# rfidbadge.net
KiCad netlist of a schematic drawn in EAGLE
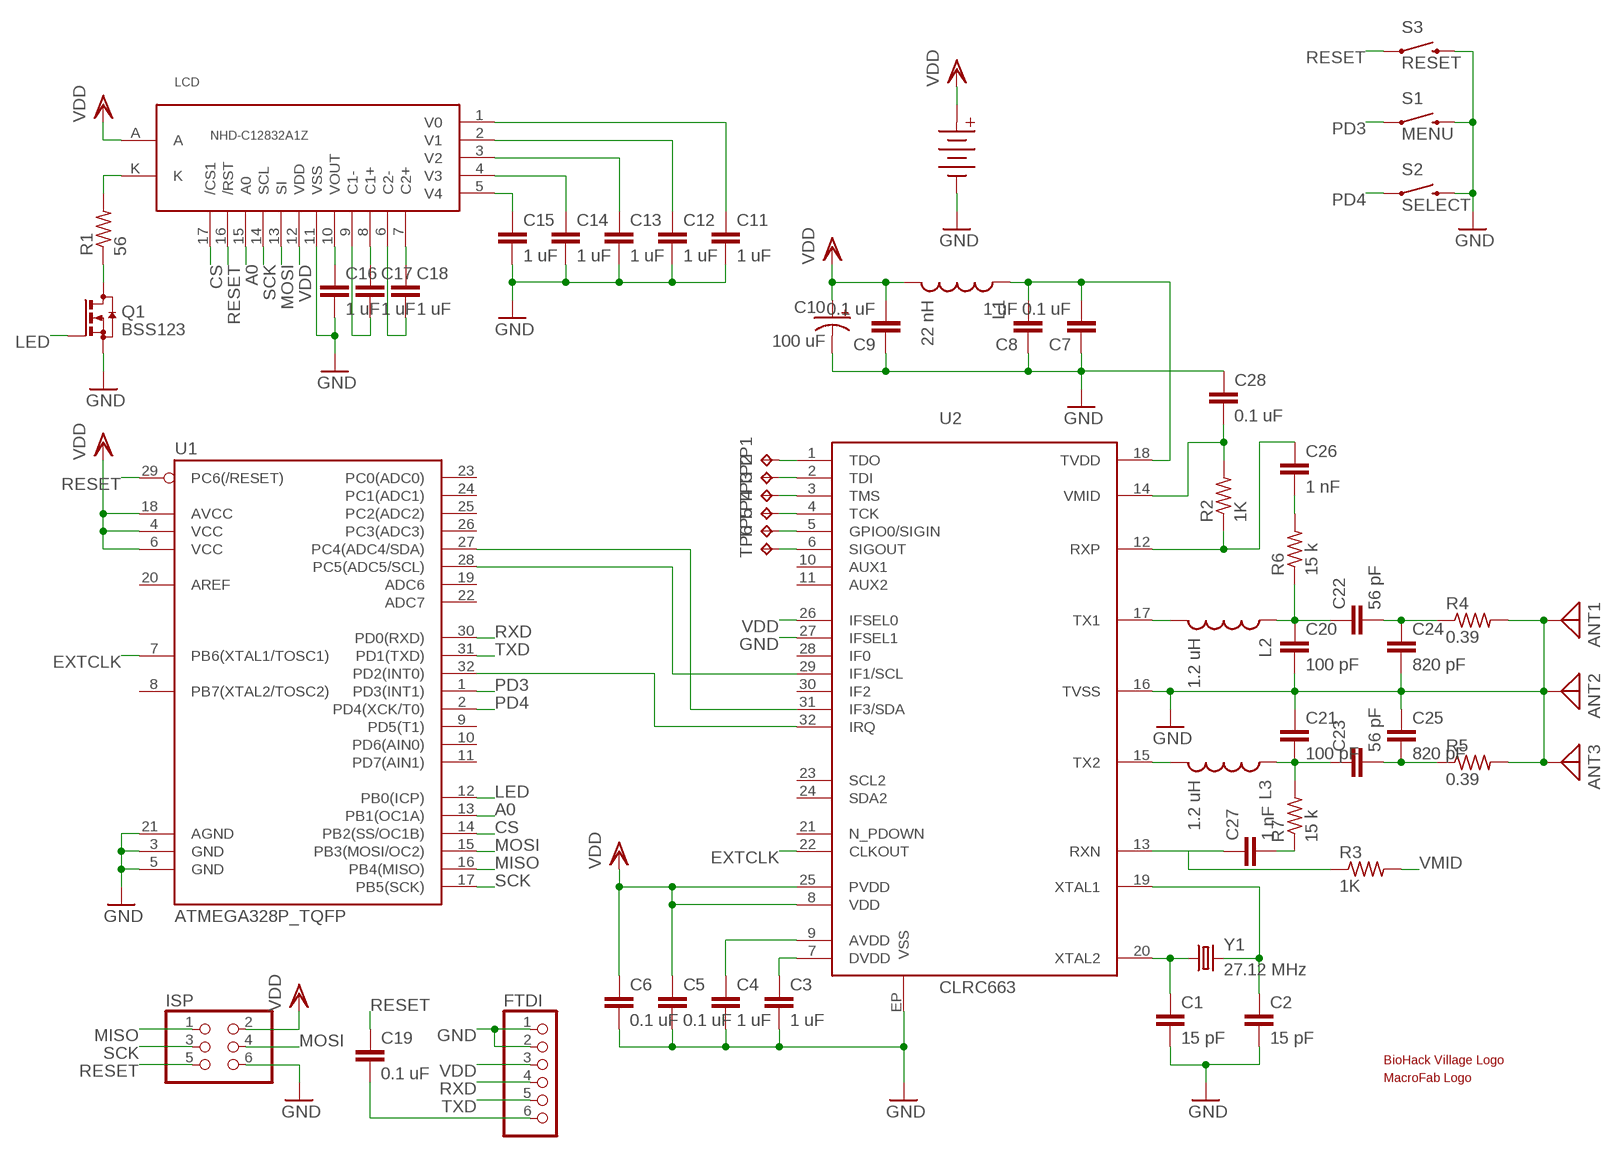
[diagram p0: schematic, sheet 1]

(export (version "E")
  (design (tool "Eeschema 10.0.6"))
  (components
    (comp (ref "ANT1")
      (value "ANTENNA")
      (footprint "eagle-import:PAD-01")
      (libsource (lib "eagle-import") (part "ANTENNA"))
    )
    (comp (ref "ANT2")
      (value "ANTENNA")
      (footprint "eagle-import:PAD-01")
      (libsource (lib "eagle-import") (part "ANTENNA"))
    )
    (comp (ref "ANT3")
      (value "ANTENNA")
      (footprint "eagle-import:PAD-01")
      (libsource (lib "eagle-import") (part "ANTENNA"))
    )
    (comp (ref "BAT")
      (value "AAA_X3")
      (footprint "eagle-import:AAA_X3")
      (libsource (lib "eagle-import") (part "AAA_X3"))
    )
    (comp (ref "C1")
      (value "15 pF")
      (footprint "eagle-import:C0603K")
      (libsource (lib "eagle-import") (part "C-EUC0603K"))
    )
    (comp (ref "C2")
      (value "15 pF")
      (footprint "eagle-import:C0603K")
      (libsource (lib "eagle-import") (part "C-EUC0603K"))
    )
    (comp (ref "C3")
      (value "1 uF")
      (footprint "eagle-import:C0603K")
      (libsource (lib "eagle-import") (part "C-EUC0603K"))
    )
    (comp (ref "C4")
      (value "1 uF")
      (footprint "eagle-import:C0603K")
      (libsource (lib "eagle-import") (part "C-EUC0603K"))
    )
    (comp (ref "C5")
      (value "0.1 uF")
      (footprint "eagle-import:C0603K")
      (libsource (lib "eagle-import") (part "C-EUC0603K"))
    )
    (comp (ref "C6")
      (value "0.1 uF")
      (footprint "eagle-import:C0603K")
      (libsource (lib "eagle-import") (part "C-EUC0603K"))
    )
    (comp (ref "C7")
      (value "0.1 uF")
      (footprint "eagle-import:C0603K")
      (libsource (lib "eagle-import") (part "C-EUC0603K"))
    )
    (comp (ref "C8")
      (value "1 uF")
      (footprint "eagle-import:C0603K")
      (libsource (lib "eagle-import") (part "C-EUC0603K"))
    )
    (comp (ref "C9")
      (value "0.1 uF")
      (footprint "eagle-import:C0603K")
      (libsource (lib "eagle-import") (part "C-EUC0603K"))
    )
    (comp (ref "C10")
      (value "100 uF")
      (footprint "eagle-import:EIA7343")
      (libsource (lib "eagle-import") (part "CAP_POL7343"))
    )
    (comp (ref "C11")
      (value "1 uF")
      (footprint "eagle-import:C0603K")
      (libsource (lib "eagle-import") (part "C-EUC0603K"))
    )
    (comp (ref "C12")
      (value "1 uF")
      (footprint "eagle-import:C0603K")
      (libsource (lib "eagle-import") (part "C-EUC0603K"))
    )
    (comp (ref "C13")
      (value "1 uF")
      (footprint "eagle-import:C0603K")
      (libsource (lib "eagle-import") (part "C-EUC0603K"))
    )
    (comp (ref "C14")
      (value "1 uF")
      (footprint "eagle-import:C0603K")
      (libsource (lib "eagle-import") (part "C-EUC0603K"))
    )
    (comp (ref "C15")
      (value "1 uF")
      (footprint "eagle-import:C0603K")
      (libsource (lib "eagle-import") (part "C-EUC0603K"))
    )
    (comp (ref "C16")
      (value "1 uF")
      (footprint "eagle-import:C0603K")
      (libsource (lib "eagle-import") (part "C-EUC0603K"))
    )
    (comp (ref "C17")
      (value "1 uF")
      (footprint "eagle-import:C0603K")
      (libsource (lib "eagle-import") (part "C-EUC0603K"))
    )
    (comp (ref "C18")
      (value "1 uF")
      (footprint "eagle-import:C0603K")
      (libsource (lib "eagle-import") (part "C-EUC0603K"))
    )
    (comp (ref "C19")
      (value "0.1 uF")
      (footprint "eagle-import:C0603K")
      (libsource (lib "eagle-import") (part "C-EUC0603K"))
    )
    (comp (ref "C20")
      (value "100 pF")
      (footprint "eagle-import:C0603K")
      (libsource (lib "eagle-import") (part "C-EUC0603K"))
    )
    (comp (ref "C21")
      (value "100 pF")
      (footprint "eagle-import:C0603K")
      (libsource (lib "eagle-import") (part "C-EUC0603K"))
    )
    (comp (ref "C22")
      (value "56 pF")
      (footprint "eagle-import:C0603K")
      (libsource (lib "eagle-import") (part "C-EUC0603K"))
    )
    (comp (ref "C23")
      (value "56 pF")
      (footprint "eagle-import:C0603K")
      (libsource (lib "eagle-import") (part "C-EUC0603K"))
    )
    (comp (ref "C24")
      (value "820 pF")
      (footprint "eagle-import:C0603K")
      (libsource (lib "eagle-import") (part "C-EUC0603K"))
    )
    (comp (ref "C25")
      (value "820 pF")
      (footprint "eagle-import:C0603K")
      (libsource (lib "eagle-import") (part "C-EUC0603K"))
    )
    (comp (ref "C26")
      (value "1 nF")
      (footprint "eagle-import:C0603K")
      (libsource (lib "eagle-import") (part "C-EUC0603K"))
    )
    (comp (ref "C27")
      (value "1 nF")
      (footprint "eagle-import:C0603K")
      (libsource (lib "eagle-import") (part "C-EUC0603K"))
    )
    (comp (ref "C28")
      (value "0.1 uF")
      (footprint "eagle-import:C0603K")
      (libsource (lib "eagle-import") (part "C-EUC0603K"))
    )
    (comp (ref "FTDI")
      (value "PINHD-1X6")
      (footprint "eagle-import:1X06")
      (libsource (lib "eagle-import") (part "PINHD-1X6"))
    )
    (comp (ref "ISP")
      (value "PINHD-2X3")
      (footprint "eagle-import:2X03")
      (libsource (lib "eagle-import") (part "PINHD-2X3"))
    )
    (comp (ref "L1")
      (value "22 nH")
      (footprint "eagle-import:0603")
      (fields (field (name "PROD_ID") "1276-6310-1-ND"))
      (libsource (lib "eagle-import") (part "INDUCTOR30OHM,1.8A"))
    )
    (comp (ref "L2")
      (value "1.2 uH")
      (footprint "eagle-import:0603")
      (fields (field (name "PROD_ID") "535-12527-1-ND"))
      (libsource (lib "eagle-import") (part "INDUCTOR30OHM,1.8A"))
    )
    (comp (ref "L3")
      (value "1.2 uH")
      (footprint "eagle-import:0603")
      (fields (field (name "PROD_ID") "535-12527-1-ND"))
      (libsource (lib "eagle-import") (part "INDUCTOR30OHM,1.8A"))
    )
    (comp (ref "LCD")
      (value "NHD-C12832A1Z")
      (footprint "eagle-import:NHD-C12832A1Z")
      (libsource (lib "eagle-import") (part "NHD-C12832A1Z"))
    )
    (comp (ref "Q1")
      (value "BSS123")
      (footprint "eagle-import:SOT23")
      (libsource (lib "eagle-import") (part "BSS123"))
    )
    (comp (ref "R1")
      (value "56")
      (footprint "eagle-import:R0603")
      (libsource (lib "eagle-import") (part "R-US_R0603"))
    )
    (comp (ref "R2")
      (value "1K")
      (footprint "eagle-import:R0603")
      (libsource (lib "eagle-import") (part "R-US_R0603"))
    )
    (comp (ref "R3")
      (value "1K")
      (footprint "eagle-import:R0603")
      (libsource (lib "eagle-import") (part "R-US_R0603"))
    )
    (comp (ref "R4")
      (value "0.39")
      (footprint "eagle-import:R0603")
      (libsource (lib "eagle-import") (part "R-US_R0603"))
    )
    (comp (ref "R5")
      (value "0.39")
      (footprint "eagle-import:R0603")
      (libsource (lib "eagle-import") (part "R-US_R0603"))
    )
    (comp (ref "R6")
      (value "15 k")
      (footprint "eagle-import:R0603")
      (libsource (lib "eagle-import") (part "R-US_R0603"))
    )
    (comp (ref "R7")
      (value "15 k")
      (footprint "eagle-import:R0603")
      (libsource (lib "eagle-import") (part "R-US_R0603"))
    )
    (comp (ref "S1")
      (value "MENU")
      (footprint "eagle-import:TACTILE_SWITCH_TALL")
      (fields (field (name "PROD_ID") "CKN9112CT-ND"))
      (libsource (lib "eagle-import") (part "SWITCH-MOMENTARY-2SMD-4"))
    )
    (comp (ref "S2")
      (value "SELECT")
      (footprint "eagle-import:TACTILE_SWITCH_TALL")
      (fields (field (name "PROD_ID") "CKN9112CT-ND"))
      (libsource (lib "eagle-import") (part "SWITCH-MOMENTARY-2SMD-4"))
    )
    (comp (ref "S3")
      (value "RESET")
      (footprint "eagle-import:TACTILE-SWITCH-1101NE")
      (fields (field (name "PROD_ID") "CKN10388CT-ND"))
      (libsource (lib "eagle-import") (part "SWITCH-MOMENTARY-2SMD-1101NE"))
    )
    (comp (ref "TP1")
      (value "TPTP06R")
      (footprint "eagle-import:TP06R")
      (libsource (lib "eagle-import") (part "TPTP06R"))
    )
    (comp (ref "TP2")
      (value "TPTP06R")
      (footprint "eagle-import:TP06R")
      (libsource (lib "eagle-import") (part "TPTP06R"))
    )
    (comp (ref "TP3")
      (value "TPTP06R")
      (footprint "eagle-import:TP06R")
      (libsource (lib "eagle-import") (part "TPTP06R"))
    )
    (comp (ref "TP4")
      (value "TPTP06R")
      (footprint "eagle-import:TP06R")
      (libsource (lib "eagle-import") (part "TPTP06R"))
    )
    (comp (ref "TP5")
      (value "TPTP06R")
      (footprint "eagle-import:TP06R")
      (libsource (lib "eagle-import") (part "TPTP06R"))
    )
    (comp (ref "TP6")
      (value "TPTP06R")
      (footprint "eagle-import:TP06R")
      (libsource (lib "eagle-import") (part "TPTP06R"))
    )
    (comp (ref "U$1")
      (value "BHVLOGO")
      (footprint "eagle-import:BHVLOGO")
      (libsource (lib "eagle-import") (part "BHVLOGO"))
    )
    (comp (ref "U$2")
      (value "MACROFABLOGO")
      (footprint "eagle-import:MACROFABLOGO")
      (libsource (lib "eagle-import") (part "MACROFABLOGO"))
    )
    (comp (ref "U1")
      (value "ATMEGA328P_TQFP")
      (footprint "eagle-import:TQFP32-08")
      (fields (field (name "PROD_ID") "ATMEGA328PB-AURCT-ND"))
      (libsource (lib "eagle-import") (part "ATMEGA328P_TQFP"))
    )
    (comp (ref "U2")
      (value "CLRC663")
      (footprint "eagle-import:QFN32")
      (libsource (lib "eagle-import") (part "CLRC663"))
    )
    (comp (ref "Y1")
      (value "27.12 MHz")
      (footprint "eagle-import:CRYSTAL-SMD-5X3")
      (fields (field (name "PROD_ID") "887-1309-1-ND"))
      (libsource (lib "eagle-import") (part "CRYSTALCRYSTAL-SMD-5X3-12.288MHZ"))
    )
  )
  (nets
    (net (code "1") (name "/A0") (class "Default")
      (node (ref "LCD") (pin "15") (pinfunction "A0_15") (pintype "bidirectional"))
      (node (ref "U1") (pin "13") (pinfunction "PB1(OC1A)_13") (pintype "bidirectional"))
    )
    (net (code "2") (name "/CS") (class "Default")
      (node (ref "LCD") (pin "17") (pinfunction "/CS1_17") (pintype "bidirectional"))
      (node (ref "U1") (pin "14") (pinfunction "PB2(SS/OC1B)_14") (pintype "bidirectional"))
    )
    (net (code "3") (name "/EXTCLK") (class "Default")
      (node (ref "U1") (pin "7") (pinfunction "PB6(XTAL1/TOSC1)_7") (pintype "bidirectional"))
      (node (ref "U2") (pin "22") (pinfunction "CLKOUT_22") (pintype "bidirectional"))
    )
    (net (code "4") (name "/LED") (class "Default")
      (node (ref "Q1") (pin "1") (pinfunction "G_1") (pintype "passive"))
      (node (ref "U1") (pin "12") (pinfunction "PB0(ICP)_12") (pintype "bidirectional"))
    )
    (net (code "5") (name "/MISO") (class "Default")
      (node (ref "ISP") (pin "1") (pinfunction "1_1") (pintype "passive"))
      (node (ref "U1") (pin "16") (pinfunction "PB4(MISO)_16") (pintype "bidirectional"))
    )
    (net (code "6") (name "/MOSI") (class "Default")
      (node (ref "ISP") (pin "4") (pinfunction "4_4") (pintype "passive"))
      (node (ref "LCD") (pin "13") (pinfunction "SI_13") (pintype "bidirectional"))
      (node (ref "U1") (pin "15") (pinfunction "PB3(MOSI/OC2)_15") (pintype "bidirectional"))
    )
    (net (code "7") (name "/PD3") (class "Default")
      (node (ref "S1") (pin "A2") (pinfunction "1_A2") (pintype "passive"))
      (node (ref "U1") (pin "1") (pinfunction "PD3(INT1)_1") (pintype "bidirectional"))
    )
    (net (code "8") (name "/PD4") (class "Default")
      (node (ref "S2") (pin "A2") (pinfunction "1_A2") (pintype "passive"))
      (node (ref "U1") (pin "2") (pinfunction "PD4(XCK/T0)_2") (pintype "bidirectional"))
    )
    (net (code "9") (name "/RESET") (class "Default")
      (node (ref "C19") (pin "1") (pinfunction "1_1") (pintype "passive"))
      (node (ref "ISP") (pin "5") (pinfunction "5_5") (pintype "passive"))
      (node (ref "LCD") (pin "16") (pinfunction "/RST_16") (pintype "bidirectional"))
      (node (ref "S3") (pin "1") (pinfunction "1_1") (pintype "passive"))
      (node (ref "U1") (pin "29") (pinfunction "PC6(/RESET)_29") (pintype "bidirectional"))
    )
    (net (code "10") (name "/RXD") (class "Default")
      (node (ref "FTDI") (pin "4") (pinfunction "4_4") (pintype "passive"))
      (node (ref "U1") (pin "30") (pinfunction "PD0(RXD)_30") (pintype "bidirectional"))
    )
    (net (code "11") (name "/SCK") (class "Default")
      (node (ref "ISP") (pin "3") (pinfunction "3_3") (pintype "passive"))
      (node (ref "LCD") (pin "14") (pinfunction "SCL_14") (pintype "bidirectional"))
      (node (ref "U1") (pin "17") (pinfunction "PB5(SCK)_17") (pintype "bidirectional"))
    )
    (net (code "12") (name "/TXD") (class "Default")
      (node (ref "FTDI") (pin "5") (pinfunction "5_5") (pintype "passive"))
      (node (ref "U1") (pin "31") (pinfunction "PD1(TXD)_31") (pintype "bidirectional"))
    )
    (net (code "13") (name "/VMID") (class "Default")
      (node (ref "C28") (pin "2") (pinfunction "2_2") (pintype "passive"))
      (node (ref "R2") (pin "2") (pinfunction "2_2") (pintype "passive"))
      (node (ref "R3") (pin "2") (pinfunction "2_2") (pintype "passive"))
      (node (ref "U2") (pin "14") (pinfunction "VMID_14") (pintype "bidirectional"))
    )
    (net (code "14") (name "GND") (class "Default")
      (node (ref "ANT1") (pin "1") (pinfunction "1_1") (pintype "output"))
      (node (ref "ANT2") (pin "1") (pinfunction "1_1") (pintype "output"))
      (node (ref "ANT3") (pin "1") (pinfunction "1_1") (pintype "output"))
      (node (ref "BAT") (pin "NEG") (pinfunction "P$1_NEG") (pintype "power_in"))
      (node (ref "C1") (pin "2") (pinfunction "2_2") (pintype "passive"))
      (node (ref "C10") (pin "C") (pinfunction "-_C") (pintype "passive"))
      (node (ref "C11") (pin "2") (pinfunction "2_2") (pintype "passive"))
      (node (ref "C12") (pin "2") (pinfunction "2_2") (pintype "passive"))
      (node (ref "C13") (pin "2") (pinfunction "2_2") (pintype "passive"))
      (node (ref "C14") (pin "2") (pinfunction "2_2") (pintype "passive"))
      (node (ref "C15") (pin "2") (pinfunction "2_2") (pintype "passive"))
      (node (ref "C16") (pin "2") (pinfunction "2_2") (pintype "passive"))
      (node (ref "C2") (pin "2") (pinfunction "2_2") (pintype "passive"))
      (node (ref "C20") (pin "2") (pinfunction "2_2") (pintype "passive"))
      (node (ref "C21") (pin "1") (pinfunction "1_1") (pintype "passive"))
      (node (ref "C24") (pin "2") (pinfunction "2_2") (pintype "passive"))
      (node (ref "C25") (pin "1") (pinfunction "1_1") (pintype "passive"))
      (node (ref "C28") (pin "1") (pinfunction "1_1") (pintype "passive"))
      (node (ref "C3") (pin "2") (pinfunction "2_2") (pintype "passive"))
      (node (ref "C4") (pin "2") (pinfunction "2_2") (pintype "passive"))
      (node (ref "C5") (pin "2") (pinfunction "2_2") (pintype "passive"))
      (node (ref "C6") (pin "2") (pinfunction "2_2") (pintype "passive"))
      (node (ref "C7") (pin "1") (pinfunction "1_1") (pintype "passive"))
      (node (ref "C8") (pin "1") (pinfunction "1_1") (pintype "passive"))
      (node (ref "C9") (pin "1") (pinfunction "1_1") (pintype "passive"))
      (node (ref "FTDI") (pin "1") (pinfunction "1_1") (pintype "passive"))
      (node (ref "FTDI") (pin "2") (pinfunction "2_2") (pintype "passive"))
      (node (ref "ISP") (pin "6") (pinfunction "6_6") (pintype "passive"))
      (node (ref "LCD") (pin "11") (pinfunction "VSS_11") (pintype "bidirectional"))
      (node (ref "Q1") (pin "2") (pinfunction "S_2") (pintype "passive"))
      (node (ref "R4") (pin "2") (pinfunction "2_2") (pintype "passive"))
      (node (ref "R5") (pin "2") (pinfunction "2_2") (pintype "passive"))
      (node (ref "S1") (pin "B2") (pinfunction "2_B2") (pintype "passive"))
      (node (ref "S2") (pin "B2") (pinfunction "2_B2") (pintype "passive"))
      (node (ref "S3") (pin "2") (pinfunction "2_2") (pintype "passive"))
      (node (ref "U1") (pin "21") (pinfunction "AGND_21") (pintype "bidirectional"))
      (node (ref "U1") (pin "3") (pinfunction "GND_3") (pintype "bidirectional"))
      (node (ref "U1") (pin "5") (pinfunction "GND_5") (pintype "bidirectional"))
      (node (ref "U2") (pin "16") (pinfunction "TVSS_16") (pintype "bidirectional"))
      (node (ref "U2") (pin "27") (pinfunction "IFSEL1_27") (pintype "bidirectional"))
      (node (ref "U2") (pin "EP") (pinfunction "VSS_EP") (pintype "bidirectional"))
    )
    (net (code "15") (name "Net-(C19-Pad2)") (class "Default")
      (node (ref "C19") (pin "2") (pinfunction "2_2") (pintype "passive"))
      (node (ref "FTDI") (pin "6") (pinfunction "6_6") (pintype "passive"))
    )
    (net (code "16") (name "Net-(C20-Pad1)") (class "Default")
      (node (ref "C20") (pin "1") (pinfunction "1_1") (pintype "passive"))
      (node (ref "C22") (pin "1") (pinfunction "1_1") (pintype "passive"))
      (node (ref "L2") (pin "1") (pinfunction "1_1") (pintype "passive"))
      (node (ref "R6") (pin "1") (pinfunction "1_1") (pintype "passive"))
    )
    (net (code "17") (name "Net-(C21-Pad2)") (class "Default")
      (node (ref "C21") (pin "2") (pinfunction "2_2") (pintype "passive"))
      (node (ref "C23") (pin "1") (pinfunction "1_1") (pintype "passive"))
      (node (ref "L3") (pin "1") (pinfunction "1_1") (pintype "passive"))
      (node (ref "R7") (pin "2") (pinfunction "2_2") (pintype "passive"))
    )
    (net (code "18") (name "Net-(C22-Pad2)") (class "Default")
      (node (ref "C22") (pin "2") (pinfunction "2_2") (pintype "passive"))
      (node (ref "C24") (pin "1") (pinfunction "1_1") (pintype "passive"))
      (node (ref "R4") (pin "1") (pinfunction "1_1") (pintype "passive"))
    )
    (net (code "19") (name "Net-(C23-Pad2)") (class "Default")
      (node (ref "C23") (pin "2") (pinfunction "2_2") (pintype "passive"))
      (node (ref "C25") (pin "2") (pinfunction "2_2") (pintype "passive"))
      (node (ref "R5") (pin "1") (pinfunction "1_1") (pintype "passive"))
    )
    (net (code "20") (name "Net-(C26-Pad2)") (class "Default")
      (node (ref "C26") (pin "2") (pinfunction "2_2") (pintype "passive"))
      (node (ref "R6") (pin "2") (pinfunction "2_2") (pintype "passive"))
    )
    (net (code "21") (name "Net-(C27-Pad2)") (class "Default")
      (node (ref "C27") (pin "2") (pinfunction "2_2") (pintype "passive"))
      (node (ref "R7") (pin "1") (pinfunction "1_1") (pintype "passive"))
    )
    (net (code "22") (name "Net-(LCD-C1+)") (class "Default")
      (node (ref "C17") (pin "1") (pinfunction "1_1") (pintype "passive"))
      (node (ref "LCD") (pin "8") (pinfunction "C1+_8") (pintype "bidirectional"))
    )
    (net (code "23") (name "Net-(LCD-C1-)") (class "Default")
      (node (ref "C17") (pin "2") (pinfunction "2_2") (pintype "passive"))
      (node (ref "LCD") (pin "9") (pinfunction "C1-_9") (pintype "bidirectional"))
    )
    (net (code "24") (name "Net-(LCD-C2+)") (class "Default")
      (node (ref "C18") (pin "1") (pinfunction "1_1") (pintype "passive"))
      (node (ref "LCD") (pin "7") (pinfunction "C2+_7") (pintype "bidirectional"))
    )
    (net (code "25") (name "Net-(LCD-C2-)") (class "Default")
      (node (ref "C18") (pin "2") (pinfunction "2_2") (pintype "passive"))
      (node (ref "LCD") (pin "6") (pinfunction "C2-_6") (pintype "bidirectional"))
    )
    (net (code "26") (name "Net-(LCD-PadK)") (class "Default")
      (node (ref "LCD") (pin "K") (pinfunction "K_K") (pintype "bidirectional"))
      (node (ref "R1") (pin "2") (pinfunction "2_2") (pintype "passive"))
    )
    (net (code "27") (name "Net-(LCD-V0)") (class "Default")
      (node (ref "C11") (pin "1") (pinfunction "1_1") (pintype "passive"))
      (node (ref "LCD") (pin "1") (pinfunction "V0_1") (pintype "bidirectional"))
    )
    (net (code "28") (name "Net-(LCD-V1)") (class "Default")
      (node (ref "C12") (pin "1") (pinfunction "1_1") (pintype "passive"))
      (node (ref "LCD") (pin "2") (pinfunction "V1_2") (pintype "bidirectional"))
    )
    (net (code "29") (name "Net-(LCD-V2)") (class "Default")
      (node (ref "C13") (pin "1") (pinfunction "1_1") (pintype "passive"))
      (node (ref "LCD") (pin "3") (pinfunction "V2_3") (pintype "bidirectional"))
    )
    (net (code "30") (name "Net-(LCD-V3)") (class "Default")
      (node (ref "C14") (pin "1") (pinfunction "1_1") (pintype "passive"))
      (node (ref "LCD") (pin "4") (pinfunction "V3_4") (pintype "bidirectional"))
    )
    (net (code "31") (name "Net-(LCD-V4)") (class "Default")
      (node (ref "C15") (pin "1") (pinfunction "1_1") (pintype "passive"))
      (node (ref "LCD") (pin "5") (pinfunction "V4_5") (pintype "bidirectional"))
    )
    (net (code "32") (name "Net-(LCD-VOUT)") (class "Default")
      (node (ref "C16") (pin "1") (pinfunction "1_1") (pintype "passive"))
      (node (ref "LCD") (pin "10") (pinfunction "VOUT_10") (pintype "bidirectional"))
    )
    (net (code "33") (name "Net-(Q1-D)") (class "Default")
      (node (ref "Q1") (pin "3") (pinfunction "D_3") (pintype "passive"))
      (node (ref "R1") (pin "1") (pinfunction "1_1") (pintype "passive"))
    )
    (net (code "34") (name "Net-(U1-PC4(ADC4{slash}SDA))") (class "Default")
      (node (ref "U1") (pin "27") (pinfunction "PC4(ADC4/SDA)_27") (pintype "bidirectional"))
      (node (ref "U2") (pin "31") (pinfunction "IF3/SDA_31") (pintype "bidirectional"))
    )
    (net (code "35") (name "Net-(U1-PC5(ADC5{slash}SCL))") (class "Default")
      (node (ref "U1") (pin "28") (pinfunction "PC5(ADC5/SCL)_28") (pintype "bidirectional"))
      (node (ref "U2") (pin "29") (pinfunction "IF1/SCL_29") (pintype "bidirectional"))
    )
    (net (code "36") (name "Net-(U1-PD2(INT0))") (class "Default")
      (node (ref "U1") (pin "32") (pinfunction "PD2(INT0)_32") (pintype "bidirectional"))
      (node (ref "U2") (pin "32") (pinfunction "IRQ_32") (pintype "bidirectional"))
    )
    (net (code "37") (name "Net-(U2-AVDD)") (class "Default")
      (node (ref "C4") (pin "1") (pinfunction "1_1") (pintype "passive"))
      (node (ref "U2") (pin "9") (pinfunction "AVDD_9") (pintype "bidirectional"))
    )
    (net (code "38") (name "Net-(U2-DVDD)") (class "Default")
      (node (ref "C3") (pin "1") (pinfunction "1_1") (pintype "passive"))
      (node (ref "U2") (pin "7") (pinfunction "DVDD_7") (pintype "bidirectional"))
    )
    (net (code "39") (name "Net-(U2-GPIO0{slash}SIGIN)") (class "Default")
      (node (ref "TP5") (pin "TP") (pinfunction "TP_TP") (pintype "input"))
      (node (ref "U2") (pin "5") (pinfunction "GPIO0/SIGIN_5") (pintype "bidirectional"))
    )
    (net (code "40") (name "Net-(U2-RXN)") (class "Default")
      (node (ref "C27") (pin "1") (pinfunction "1_1") (pintype "passive"))
      (node (ref "R3") (pin "1") (pinfunction "1_1") (pintype "passive"))
      (node (ref "U2") (pin "13") (pinfunction "RXN_13") (pintype "bidirectional"))
    )
    (net (code "41") (name "Net-(U2-RXP)") (class "Default")
      (node (ref "C26") (pin "1") (pinfunction "1_1") (pintype "passive"))
      (node (ref "R2") (pin "1") (pinfunction "1_1") (pintype "passive"))
      (node (ref "U2") (pin "12") (pinfunction "RXP_12") (pintype "bidirectional"))
    )
    (net (code "42") (name "Net-(U2-SIGOUT)") (class "Default")
      (node (ref "TP6") (pin "TP") (pinfunction "TP_TP") (pintype "input"))
      (node (ref "U2") (pin "6") (pinfunction "SIGOUT_6") (pintype "bidirectional"))
    )
    (net (code "43") (name "Net-(U2-TCK)") (class "Default")
      (node (ref "TP4") (pin "TP") (pinfunction "TP_TP") (pintype "input"))
      (node (ref "U2") (pin "4") (pinfunction "TCK_4") (pintype "bidirectional"))
    )
    (net (code "44") (name "Net-(U2-TDI)") (class "Default")
      (node (ref "TP2") (pin "TP") (pinfunction "TP_TP") (pintype "input"))
      (node (ref "U2") (pin "2") (pinfunction "TDI_2") (pintype "bidirectional"))
    )
    (net (code "45") (name "Net-(U2-TDO)") (class "Default")
      (node (ref "TP1") (pin "TP") (pinfunction "TP_TP") (pintype "input"))
      (node (ref "U2") (pin "1") (pinfunction "TDO_1") (pintype "bidirectional"))
    )
    (net (code "46") (name "Net-(U2-TMS)") (class "Default")
      (node (ref "TP3") (pin "TP") (pinfunction "TP_TP") (pintype "input"))
      (node (ref "U2") (pin "3") (pinfunction "TMS_3") (pintype "bidirectional"))
    )
    (net (code "47") (name "Net-(U2-TVDD)") (class "Default")
      (node (ref "C7") (pin "2") (pinfunction "2_2") (pintype "passive"))
      (node (ref "C8") (pin "2") (pinfunction "2_2") (pintype "passive"))
      (node (ref "L1") (pin "1") (pinfunction "1_1") (pintype "passive"))
      (node (ref "U2") (pin "18") (pinfunction "TVDD_18") (pintype "bidirectional"))
    )
    (net (code "48") (name "Net-(U2-TX1)") (class "Default")
      (node (ref "L2") (pin "2") (pinfunction "2_2") (pintype "passive"))
      (node (ref "U2") (pin "17") (pinfunction "TX1_17") (pintype "bidirectional"))
    )
    (net (code "49") (name "Net-(U2-TX2)") (class "Default")
      (node (ref "L3") (pin "2") (pinfunction "2_2") (pintype "passive"))
      (node (ref "U2") (pin "15") (pinfunction "TX2_15") (pintype "bidirectional"))
    )
    (net (code "50") (name "Net-(U2-XTAL1)") (class "Default")
      (node (ref "C2") (pin "1") (pinfunction "1_1") (pintype "passive"))
      (node (ref "U2") (pin "19") (pinfunction "XTAL1_19") (pintype "bidirectional"))
      (node (ref "Y1") (pin "3") (pinfunction "2_3") (pintype "passive"))
    )
    (net (code "51") (name "Net-(U2-XTAL2)") (class "Default")
      (node (ref "C1") (pin "1") (pinfunction "1_1") (pintype "passive"))
      (node (ref "U2") (pin "20") (pinfunction "XTAL2_20") (pintype "bidirectional"))
      (node (ref "Y1") (pin "1") (pinfunction "1_1") (pintype "passive"))
    )
    (net (code "52") (name "VDD") (class "Default")
      (node (ref "BAT") (pin "POS") (pinfunction "P$2_POS") (pintype "power_in"))
      (node (ref "C10") (pin "A") (pinfunction "+_A") (pintype "passive"))
      (node (ref "C5") (pin "1") (pinfunction "1_1") (pintype "passive"))
      (node (ref "C6") (pin "1") (pinfunction "1_1") (pintype "passive"))
      (node (ref "C9") (pin "2") (pinfunction "2_2") (pintype "passive"))
      (node (ref "FTDI") (pin "3") (pinfunction "3_3") (pintype "passive"))
      (node (ref "ISP") (pin "2") (pinfunction "2_2") (pintype "passive"))
      (node (ref "L1") (pin "2") (pinfunction "2_2") (pintype "passive"))
      (node (ref "LCD") (pin "12") (pinfunction "VDD_12") (pintype "bidirectional"))
      (node (ref "LCD") (pin "A") (pinfunction "A_A") (pintype "bidirectional"))
      (node (ref "U1") (pin "18") (pinfunction "AVCC_18") (pintype "bidirectional"))
      (node (ref "U1") (pin "4") (pinfunction "VCC_4") (pintype "bidirectional"))
      (node (ref "U1") (pin "6") (pinfunction "VCC_6") (pintype "bidirectional"))
      (node (ref "U2") (pin "25") (pinfunction "PVDD_25") (pintype "bidirectional"))
      (node (ref "U2") (pin "26") (pinfunction "IFSEL0_26") (pintype "bidirectional"))
      (node (ref "U2") (pin "8") (pinfunction "VDD_8") (pintype "bidirectional"))
    )
    (net (code "53") (name "unconnected-(U1-ADC6-Pad19)") (class "Default")
      (node (ref "U1") (pin "19") (pinfunction "ADC6_19") (pintype "bidirectional"))
    )
    (net (code "54") (name "unconnected-(U1-ADC7-Pad22)") (class "Default")
      (node (ref "U1") (pin "22") (pinfunction "ADC7_22") (pintype "bidirectional"))
    )
    (net (code "55") (name "unconnected-(U1-AREF-Pad20)") (class "Default")
      (node (ref "U1") (pin "20") (pinfunction "AREF_20") (pintype "bidirectional"))
    )
    (net (code "56") (name "unconnected-(U1-PB7(XTAL2{slash}TOSC2)-Pad8)") (class "Default")
      (node (ref "U1") (pin "8") (pinfunction "PB7(XTAL2/TOSC2)_8") (pintype "bidirectional"))
    )
    (net (code "57") (name "unconnected-(U1-PC0(ADC0)-Pad23)") (class "Default")
      (node (ref "U1") (pin "23") (pinfunction "PC0(ADC0)_23") (pintype "bidirectional"))
    )
    (net (code "58") (name "unconnected-(U1-PC1(ADC1)-Pad24)") (class "Default")
      (node (ref "U1") (pin "24") (pinfunction "PC1(ADC1)_24") (pintype "bidirectional"))
    )
    (net (code "59") (name "unconnected-(U1-PC2(ADC2)-Pad25)") (class "Default")
      (node (ref "U1") (pin "25") (pinfunction "PC2(ADC2)_25") (pintype "bidirectional"))
    )
    (net (code "60") (name "unconnected-(U1-PC3(ADC3)-Pad26)") (class "Default")
      (node (ref "U1") (pin "26") (pinfunction "PC3(ADC3)_26") (pintype "bidirectional"))
    )
    (net (code "61") (name "unconnected-(U1-PD5(T1)-Pad9)") (class "Default")
      (node (ref "U1") (pin "9") (pinfunction "PD5(T1)_9") (pintype "bidirectional"))
    )
    (net (code "62") (name "unconnected-(U1-PD6(AIN0)-Pad10)") (class "Default")
      (node (ref "U1") (pin "10") (pinfunction "PD6(AIN0)_10") (pintype "bidirectional"))
    )
    (net (code "63") (name "unconnected-(U1-PD7(AIN1)-Pad11)") (class "Default")
      (node (ref "U1") (pin "11") (pinfunction "PD7(AIN1)_11") (pintype "bidirectional"))
    )
    (net (code "64") (name "unconnected-(U2-AUX1-Pad10)") (class "Default")
      (node (ref "U2") (pin "10") (pinfunction "AUX1_10") (pintype "bidirectional"))
    )
    (net (code "65") (name "unconnected-(U2-AUX2-Pad11)") (class "Default")
      (node (ref "U2") (pin "11") (pinfunction "AUX2_11") (pintype "bidirectional"))
    )
    (net (code "66") (name "unconnected-(U2-IF0-Pad28)") (class "Default")
      (node (ref "U2") (pin "28") (pinfunction "IF0_28") (pintype "bidirectional"))
    )
    (net (code "67") (name "unconnected-(U2-IF2-Pad30)") (class "Default")
      (node (ref "U2") (pin "30") (pinfunction "IF2_30") (pintype "bidirectional"))
    )
    (net (code "68") (name "unconnected-(U2-N_PDOWN-Pad21)") (class "Default")
      (node (ref "U2") (pin "21") (pinfunction "N_PDOWN_21") (pintype "bidirectional"))
    )
    (net (code "69") (name "unconnected-(U2-SCL2-Pad23)") (class "Default")
      (node (ref "U2") (pin "23") (pinfunction "SCL2_23") (pintype "bidirectional"))
    )
    (net (code "70") (name "unconnected-(U2-SDA2-Pad24)") (class "Default")
      (node (ref "U2") (pin "24") (pinfunction "SDA2_24") (pintype "bidirectional"))
    )
  )
)
